# Sensor_LF.net
KiCad netlist of a schematic drawn in EAGLE
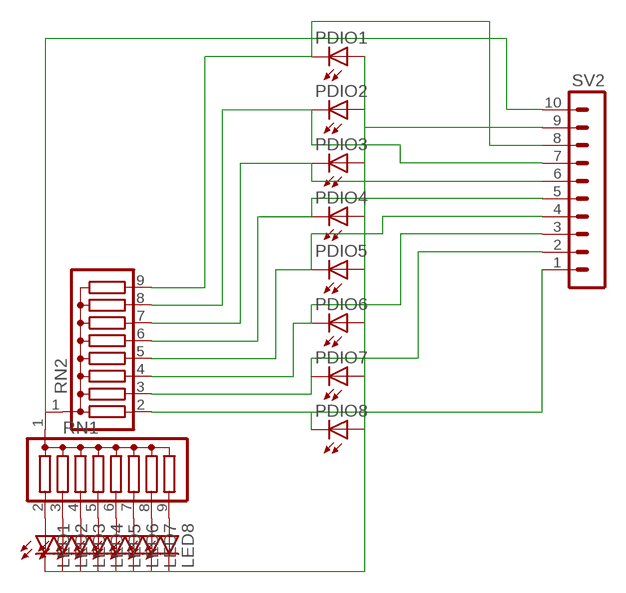
[diagram p0: schematic, sheet 1]

(export (version "E")
  (design (tool "Eeschema 10.0.6"))
  (components
    (comp (ref "LED1")
      (value "LED3MM")
      (footprint "eagle-import:LED3MM")
      (libsource (lib "eagle-import") (part "LED3MM"))
    )
    (comp (ref "LED2")
      (value "LED3MM")
      (footprint "eagle-import:LED3MM")
      (libsource (lib "eagle-import") (part "LED3MM"))
    )
    (comp (ref "LED3")
      (value "LED3MM")
      (footprint "eagle-import:LED3MM")
      (libsource (lib "eagle-import") (part "LED3MM"))
    )
    (comp (ref "LED4")
      (value "LED3MM")
      (footprint "eagle-import:LED3MM")
      (libsource (lib "eagle-import") (part "LED3MM"))
    )
    (comp (ref "LED5")
      (value "LED3MM")
      (footprint "eagle-import:LED3MM")
      (libsource (lib "eagle-import") (part "LED3MM"))
    )
    (comp (ref "LED6")
      (value "LED3MM")
      (footprint "eagle-import:LED3MM")
      (libsource (lib "eagle-import") (part "LED3MM"))
    )
    (comp (ref "LED7")
      (value "LED3MM")
      (footprint "eagle-import:LED3MM")
      (libsource (lib "eagle-import") (part "LED3MM"))
    )
    (comp (ref "LED8")
      (value "LED3MM")
      (footprint "eagle-import:LED3MM")
      (libsource (lib "eagle-import") (part "LED3MM"))
    )
    (comp (ref "PDIO1")
      (value "LED3MM")
      (footprint "eagle-import:LED3MM")
      (libsource (lib "eagle-import") (part "LED3MM"))
    )
    (comp (ref "PDIO2")
      (value "LED3MM")
      (footprint "eagle-import:LED3MM")
      (libsource (lib "eagle-import") (part "LED3MM"))
    )
    (comp (ref "PDIO3")
      (value "LED3MM")
      (footprint "eagle-import:LED3MM")
      (libsource (lib "eagle-import") (part "LED3MM"))
    )
    (comp (ref "PDIO4")
      (value "LED3MM")
      (footprint "eagle-import:LED3MM")
      (libsource (lib "eagle-import") (part "LED3MM"))
    )
    (comp (ref "PDIO5")
      (value "LED3MM")
      (footprint "eagle-import:LED3MM")
      (libsource (lib "eagle-import") (part "LED3MM"))
    )
    (comp (ref "PDIO6")
      (value "LED3MM")
      (footprint "eagle-import:LED3MM")
      (libsource (lib "eagle-import") (part "LED3MM"))
    )
    (comp (ref "PDIO7")
      (value "LED3MM")
      (footprint "eagle-import:LED3MM")
      (libsource (lib "eagle-import") (part "LED3MM"))
    )
    (comp (ref "PDIO8")
      (value "LED3MM")
      (footprint "eagle-import:LED3MM")
      (libsource (lib "eagle-import") (part "LED3MM"))
    )
    (comp (ref "RN1")
      (value "G08R")
      (footprint "eagle-import:SIL9")
      (libsource (lib "eagle-import") (part "G08R"))
    )
    (comp (ref "RN2")
      (value "G08R")
      (footprint "eagle-import:SIL9")
      (libsource (lib "eagle-import") (part "G08R"))
    )
    (comp (ref "SV2")
      (value "MA10-1")
      (footprint "eagle-import:MA10-1")
      (libsource (lib "eagle-import") (part "MA10-1"))
    )
  )
  (nets
    (net (code "1") (name "Net-(LED1-C)") (class "Default")
      (node (ref "LED1") (pin "K") (pinfunction "C_K") (pintype "passive"))
      (node (ref "LED2") (pin "K") (pinfunction "C_K") (pintype "passive"))
      (node (ref "LED3") (pin "K") (pinfunction "C_K") (pintype "passive"))
      (node (ref "LED4") (pin "K") (pinfunction "C_K") (pintype "passive"))
      (node (ref "LED5") (pin "K") (pinfunction "C_K") (pintype "passive"))
      (node (ref "LED6") (pin "K") (pinfunction "C_K") (pintype "passive"))
      (node (ref "LED7") (pin "K") (pinfunction "C_K") (pintype "passive"))
      (node (ref "LED8") (pin "K") (pinfunction "C_K") (pintype "passive"))
      (node (ref "PDIO1") (pin "A") (pinfunction "A_A") (pintype "passive"))
      (node (ref "PDIO2") (pin "A") (pinfunction "A_A") (pintype "passive"))
      (node (ref "PDIO3") (pin "A") (pinfunction "A_A") (pintype "passive"))
      (node (ref "PDIO4") (pin "A") (pinfunction "A_A") (pintype "passive"))
      (node (ref "PDIO5") (pin "A") (pinfunction "A_A") (pintype "passive"))
      (node (ref "PDIO6") (pin "A") (pinfunction "A_A") (pintype "passive"))
      (node (ref "PDIO7") (pin "A") (pinfunction "A_A") (pintype "passive"))
      (node (ref "PDIO8") (pin "A") (pinfunction "A_A") (pintype "passive"))
      (node (ref "SV2") (pin "9") (pinfunction "9_9") (pintype "passive"))
    )
    (net (code "2") (name "Net-(LED1-PadA)") (class "Default")
      (node (ref "LED1") (pin "A") (pinfunction "A_A") (pintype "passive"))
      (node (ref "RN1") (pin "2") (pinfunction "2_2") (pintype "passive"))
    )
    (net (code "3") (name "Net-(LED2-PadA)") (class "Default")
      (node (ref "LED2") (pin "A") (pinfunction "A_A") (pintype "passive"))
      (node (ref "RN1") (pin "3") (pinfunction "3_3") (pintype "passive"))
    )
    (net (code "4") (name "Net-(LED3-PadA)") (class "Default")
      (node (ref "LED3") (pin "A") (pinfunction "A_A") (pintype "passive"))
      (node (ref "RN1") (pin "4") (pinfunction "4_4") (pintype "passive"))
    )
    (net (code "5") (name "Net-(LED4-PadA)") (class "Default")
      (node (ref "LED4") (pin "A") (pinfunction "A_A") (pintype "passive"))
      (node (ref "RN1") (pin "5") (pinfunction "5_5") (pintype "passive"))
    )
    (net (code "6") (name "Net-(LED5-PadA)") (class "Default")
      (node (ref "LED5") (pin "A") (pinfunction "A_A") (pintype "passive"))
      (node (ref "RN1") (pin "6") (pinfunction "6_6") (pintype "passive"))
    )
    (net (code "7") (name "Net-(LED6-PadA)") (class "Default")
      (node (ref "LED6") (pin "A") (pinfunction "A_A") (pintype "passive"))
      (node (ref "RN1") (pin "7") (pinfunction "7_7") (pintype "passive"))
    )
    (net (code "8") (name "Net-(LED7-PadA)") (class "Default")
      (node (ref "LED7") (pin "A") (pinfunction "A_A") (pintype "passive"))
      (node (ref "RN1") (pin "8") (pinfunction "8_8") (pintype "passive"))
    )
    (net (code "9") (name "Net-(LED8-PadA)") (class "Default")
      (node (ref "LED8") (pin "A") (pinfunction "A_A") (pintype "passive"))
      (node (ref "RN1") (pin "9") (pinfunction "9_9") (pintype "passive"))
    )
    (net (code "10") (name "Net-(PDIO1-C)") (class "Default")
      (node (ref "PDIO1") (pin "K") (pinfunction "C_K") (pintype "passive"))
      (node (ref "RN2") (pin "9") (pinfunction "9_9") (pintype "passive"))
      (node (ref "SV2") (pin "8") (pinfunction "8_8") (pintype "passive"))
    )
    (net (code "11") (name "Net-(PDIO2-C)") (class "Default")
      (node (ref "PDIO2") (pin "K") (pinfunction "C_K") (pintype "passive"))
      (node (ref "RN2") (pin "8") (pinfunction "8_8") (pintype "passive"))
      (node (ref "SV2") (pin "7") (pinfunction "7_7") (pintype "passive"))
    )
    (net (code "12") (name "Net-(PDIO3-C)") (class "Default")
      (node (ref "PDIO3") (pin "K") (pinfunction "C_K") (pintype "passive"))
      (node (ref "RN2") (pin "7") (pinfunction "7_7") (pintype "passive"))
      (node (ref "SV2") (pin "6") (pinfunction "6_6") (pintype "passive"))
    )
    (net (code "13") (name "Net-(PDIO4-C)") (class "Default")
      (node (ref "PDIO4") (pin "K") (pinfunction "C_K") (pintype "passive"))
      (node (ref "RN2") (pin "6") (pinfunction "6_6") (pintype "passive"))
      (node (ref "SV2") (pin "5") (pinfunction "5_5") (pintype "passive"))
    )
    (net (code "14") (name "Net-(PDIO5-C)") (class "Default")
      (node (ref "PDIO5") (pin "K") (pinfunction "C_K") (pintype "passive"))
      (node (ref "RN2") (pin "5") (pinfunction "5_5") (pintype "passive"))
      (node (ref "SV2") (pin "4") (pinfunction "4_4") (pintype "passive"))
    )
    (net (code "15") (name "Net-(PDIO6-C)") (class "Default")
      (node (ref "PDIO6") (pin "K") (pinfunction "C_K") (pintype "passive"))
      (node (ref "RN2") (pin "4") (pinfunction "4_4") (pintype "passive"))
      (node (ref "SV2") (pin "3") (pinfunction "3_3") (pintype "passive"))
    )
    (net (code "16") (name "Net-(PDIO7-C)") (class "Default")
      (node (ref "PDIO7") (pin "K") (pinfunction "C_K") (pintype "passive"))
      (node (ref "RN2") (pin "3") (pinfunction "3_3") (pintype "passive"))
      (node (ref "SV2") (pin "2") (pinfunction "2_2") (pintype "passive"))
    )
    (net (code "17") (name "Net-(PDIO8-C)") (class "Default")
      (node (ref "PDIO8") (pin "K") (pinfunction "C_K") (pintype "passive"))
      (node (ref "RN2") (pin "2") (pinfunction "2_2") (pintype "passive"))
      (node (ref "SV2") (pin "1") (pinfunction "1_1") (pintype "passive"))
    )
    (net (code "18") (name "Net-(RN1-Pad1)") (class "Default")
      (node (ref "RN1") (pin "1") (pinfunction "1_1") (pintype "passive"))
      (node (ref "RN2") (pin "1") (pinfunction "1_1") (pintype "passive"))
      (node (ref "SV2") (pin "10") (pinfunction "10_10") (pintype "passive"))
    )
  )
)
